# mosfet.net
KiCad netlist of a schematic drawn in EAGLE
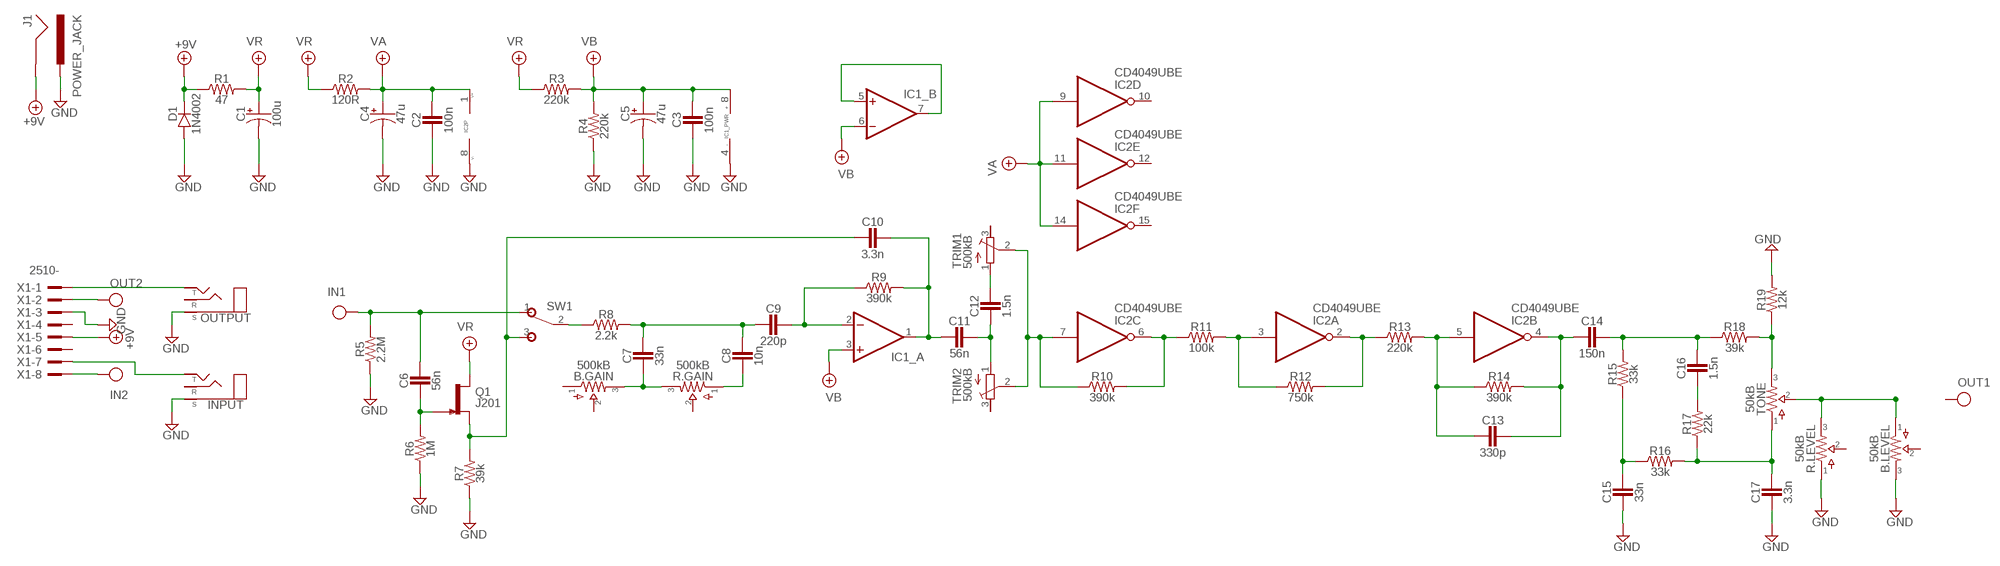
[diagram p0: schematic, sheet 1]

(export (version "E")
  (design (tool "Eeschema 10.0.6"))
  (components
    (comp (ref "B.GAIN")
      (value "500kB")
      (footprint "eagle-import:16MM")
      (libsource (lib "eagle-import") (part "POTS16MM"))
    )
    (comp (ref "B.LEVEL")
      (value "50kB")
      (footprint "eagle-import:16MM")
      (libsource (lib "eagle-import") (part "POTS16MM"))
    )
    (comp (ref "C1")
      (value "100u")
      (footprint "eagle-import:050_020")
      (libsource (lib "eagle-import") (part "0500"))
    )
    (comp (ref "C2")
      (value "100n")
      (footprint "eagle-import:050X030_025_2")
      (libsource (lib "eagle-import") (part "CER/FILM2"))
    )
    (comp (ref "C3")
      (value "100n")
      (footprint "eagle-import:050X030_025_2")
      (libsource (lib "eagle-import") (part "CER/FILM2"))
    )
    (comp (ref "C4")
      (value "47u")
      (footprint "eagle-import:050_020")
      (libsource (lib "eagle-import") (part "0500"))
    )
    (comp (ref "C5")
      (value "47u")
      (footprint "eagle-import:050_020")
      (libsource (lib "eagle-import") (part "0500"))
    )
    (comp (ref "C6")
      (value "56n")
      (footprint "eagle-import:BOX_SMALL")
      (libsource (lib "eagle-import") (part "CER/FILMBOX.1"))
    )
    (comp (ref "C7")
      (value "33n")
      (footprint "eagle-import:BOX_SMALL")
      (libsource (lib "eagle-import") (part "CER/FILMBOX.1"))
    )
    (comp (ref "C8")
      (value "10n")
      (footprint "eagle-import:BOX_SMALL")
      (libsource (lib "eagle-import") (part "CER/FILMBOX.1"))
    )
    (comp (ref "C9")
      (value "220p")
      (footprint "eagle-import:050X030_025_2")
      (libsource (lib "eagle-import") (part "CER/FILM2"))
    )
    (comp (ref "C10")
      (value "3.3n")
      (footprint "eagle-import:050X030_025_2")
      (libsource (lib "eagle-import") (part "CER/FILM2"))
    )
    (comp (ref "C11")
      (value "56n")
      (footprint "eagle-import:050X030_025_2")
      (libsource (lib "eagle-import") (part "CER/FILM2"))
    )
    (comp (ref "C12")
      (value "1.5n")
      (footprint "eagle-import:050X030_025_2")
      (libsource (lib "eagle-import") (part "CER/FILM2"))
    )
    (comp (ref "C13")
      (value "330p")
      (footprint "eagle-import:050X030_025_2")
      (libsource (lib "eagle-import") (part "CER/FILM2"))
    )
    (comp (ref "C14")
      (value "150n")
      (footprint "eagle-import:050X030_025_2")
      (libsource (lib "eagle-import") (part "CER/FILM2"))
    )
    (comp (ref "C15")
      (value "33n")
      (footprint "eagle-import:050X030_025_2")
      (libsource (lib "eagle-import") (part "CER/FILM2"))
    )
    (comp (ref "C16")
      (value "1.5n")
      (footprint "eagle-import:050X030_025_2")
      (libsource (lib "eagle-import") (part "CER/FILM2"))
    )
    (comp (ref "C17")
      (value "3.3n")
      (footprint "eagle-import:050X030_025_2")
      (libsource (lib "eagle-import") (part "CER/FILM2"))
    )
    (comp (ref "D1")
      (value "1N4002")
      (footprint "eagle-import:DO41-2")
      (libsource (lib "eagle-import") (part "DO41.2"))
    )
    (comp (ref "IC1")
      (value "DUALTH")
      (footprint "eagle-import:DIL0")
      (libsource (lib "eagle-import") (part "DUALTH"))
    )
    (comp (ref "IC2")
      (value "CD4049UBE")
      (footprint "eagle-import:DIL16")
      (libsource (lib "eagle-import") (part "CD4049UBE"))
    )
    (comp (ref "INPUT")
      (value "STEREONMJ")
      (footprint "eagle-import:NMJ6HCD2")
      (libsource (lib "eagle-import") (part "STEREONMJ"))
    )
    (comp (ref "J1")
      (value "POWER_JACK")
      (footprint "eagle-import:POWER_JACK_PTH")
      (libsource (lib "eagle-import") (part "POWER_JACK"))
    )
    (comp (ref "OUTPUT")
      (value "STEREONMJ")
      (footprint "eagle-import:NMJ6HCD2")
      (libsource (lib "eagle-import") (part "STEREONMJ"))
    )
    (comp (ref "Q1")
      (value "J201")
      (footprint "eagle-import:TO92-")
      (libsource (lib "eagle-import") (part "J201"))
    )
    (comp (ref "R.GAIN")
      (value "500kB")
      (footprint "eagle-import:16MM")
      (libsource (lib "eagle-import") (part "POTS16MM"))
    )
    (comp (ref "R.LEVEL")
      (value "50kB")
      (footprint "eagle-import:16MM")
      (libsource (lib "eagle-import") (part "POTS16MM"))
    )
    (comp (ref "R1")
      (value "47")
      (footprint "eagle-import:R0207_3")
      (libsource (lib "eagle-import") (part "R_.3B"))
    )
    (comp (ref "R2")
      (value "120R")
      (footprint "eagle-import:R0207_3")
      (libsource (lib "eagle-import") (part "R_.3B"))
    )
    (comp (ref "R3")
      (value "220k")
      (footprint "eagle-import:R0207_3")
      (libsource (lib "eagle-import") (part "R_.3B"))
    )
    (comp (ref "R4")
      (value "220k")
      (footprint "eagle-import:R0207_3")
      (libsource (lib "eagle-import") (part "R_.3B"))
    )
    (comp (ref "R5")
      (value "2.2M")
      (footprint "eagle-import:R0207_3")
      (libsource (lib "eagle-import") (part "R_.3B"))
    )
    (comp (ref "R6")
      (value "1M")
      (footprint "eagle-import:R0207_3")
      (libsource (lib "eagle-import") (part "R_.3B"))
    )
    (comp (ref "R7")
      (value "39k")
      (footprint "eagle-import:R0207_3")
      (libsource (lib "eagle-import") (part "R_.3B"))
    )
    (comp (ref "R8")
      (value "2.2k")
      (footprint "eagle-import:R0207_3")
      (libsource (lib "eagle-import") (part "R_.3B"))
    )
    (comp (ref "R9")
      (value "390k")
      (footprint "eagle-import:R0207_3")
      (libsource (lib "eagle-import") (part "R_.3B"))
    )
    (comp (ref "R10")
      (value "390k")
      (footprint "eagle-import:R0207_3")
      (libsource (lib "eagle-import") (part "R_.3B"))
    )
    (comp (ref "R11")
      (value "100k")
      (footprint "eagle-import:R0207_3")
      (libsource (lib "eagle-import") (part "R_.3B"))
    )
    (comp (ref "R12")
      (value "750k")
      (footprint "eagle-import:R0207_3")
      (libsource (lib "eagle-import") (part "R_.3B"))
    )
    (comp (ref "R13")
      (value "220k")
      (footprint "eagle-import:R0207_3")
      (libsource (lib "eagle-import") (part "R_.3B"))
    )
    (comp (ref "R14")
      (value "390k")
      (footprint "eagle-import:R0207_3")
      (libsource (lib "eagle-import") (part "R_.3B"))
    )
    (comp (ref "R15")
      (value "33k")
      (footprint "eagle-import:R0207_3")
      (libsource (lib "eagle-import") (part "R_.3B"))
    )
    (comp (ref "R16")
      (value "33k")
      (footprint "eagle-import:R0207_3")
      (libsource (lib "eagle-import") (part "R_.3B"))
    )
    (comp (ref "R17")
      (value "22k")
      (footprint "eagle-import:R0207_3")
      (libsource (lib "eagle-import") (part "R_.3B"))
    )
    (comp (ref "R18")
      (value "39k")
      (footprint "eagle-import:R0207_3")
      (libsource (lib "eagle-import") (part "R_.3B"))
    )
    (comp (ref "R19")
      (value "12k")
      (footprint "eagle-import:R0207_3")
      (libsource (lib "eagle-import") (part "R_.3B"))
    )
    (comp (ref "SW1")
      (value "SPDT")
      (footprint "eagle-import:M9040P")
      (libsource (lib "eagle-import") (part "SPDT"))
    )
    (comp (ref "TONE")
      (value "50kB")
      (footprint "eagle-import:16MM")
      (libsource (lib "eagle-import") (part "POTS16MM"))
    )
    (comp (ref "TRIM1")
      (value "500kB")
      (footprint "eagle-import:RTRIM3296W")
      (libsource (lib "eagle-import") (part "R-TRIMM3296W"))
    )
    (comp (ref "TRIM2")
      (value "500kB")
      (footprint "eagle-import:RTRIM3296W")
      (libsource (lib "eagle-import") (part "R-TRIMM3296W"))
    )
    (comp (ref "X1")
      (value "2510-")
      (footprint "eagle-import:PAK100_2500-10")
      (fields (field (name "MF") "3M") (field (name "MPN") "2510-6002UB"))
      (libsource (lib "eagle-import") (part "2510-"))
    )
  )
  (nets
    (net (code "1") (name "+9V") (class "Default")
      (node (ref "D1") (pin "C") (pinfunction "C_C") (pintype "passive"))
      (node (ref "J1") (pin "GND") (pinfunction "GND_GND") (pintype "bidirectional"))
      (node (ref "R1") (pin "1") (pinfunction "1_1") (pintype "passive"))
      (node (ref "X1") (pin "5") (pinfunction "KL_5") (pintype "passive"))
    )
    (net (code "2") (name "GND") (class "Default")
      (node (ref "B.LEVEL") (pin "3") (pinfunction "3_3") (pintype "passive"))
      (node (ref "C1") (pin "-") (pinfunction "-_-") (pintype "passive"))
      (node (ref "C15") (pin "1") (pinfunction "1_1") (pintype "passive"))
      (node (ref "C17") (pin "1") (pinfunction "1_1") (pintype "passive"))
      (node (ref "C2") (pin "1") (pinfunction "1_1") (pintype "passive"))
      (node (ref "C3") (pin "1") (pinfunction "1_1") (pintype "passive"))
      (node (ref "C4") (pin "-") (pinfunction "-_-") (pintype "passive"))
      (node (ref "C5") (pin "-") (pinfunction "-_-") (pintype "passive"))
      (node (ref "D1") (pin "A") (pinfunction "A_A") (pintype "passive"))
      (node (ref "IC1") (pin "4") (pinfunction "V-_4") (pintype "power_in"))
      (node (ref "IC2") (pin "8") (pinfunction "VSS_8") (pintype "power_in"))
      (node (ref "INPUT") (pin "S") (pinfunction "S_S") (pintype "passive"))
      (node (ref "J1") (pin "PWR") (pinfunction "PWR_PWR") (pintype "bidirectional"))
      (node (ref "OUTPUT") (pin "S") (pinfunction "S_S") (pintype "passive"))
      (node (ref "R.LEVEL") (pin "1") (pinfunction "1_1") (pintype "passive"))
      (node (ref "R19") (pin "2") (pinfunction "2_2") (pintype "passive"))
      (node (ref "R4") (pin "1") (pinfunction "1_1") (pintype "passive"))
      (node (ref "R5") (pin "1") (pinfunction "1_1") (pintype "passive"))
      (node (ref "R6") (pin "1") (pinfunction "1_1") (pintype "passive"))
      (node (ref "R7") (pin "1") (pinfunction "1_1") (pintype "passive"))
      (node (ref "X1") (pin "3") (pinfunction "KL_3") (pintype "passive"))
    )
    (net (code "3") (name "IN") (class "Default")
      (node (ref "C6") (pin "2") (pinfunction "2_2") (pintype "passive"))
      (node (ref "R5") (pin "2") (pinfunction "2_2") (pintype "passive"))
      (node (ref "SW1") (pin "1") (pinfunction "O_1") (pintype "passive"))
      (node (ref "X1") (pin "8") (pinfunction "KL_8") (pintype "passive"))
    )
    (net (code "4") (name "Net-(B.GAIN-Pad3)") (class "Default")
      (node (ref "B.GAIN") (pin "3") (pinfunction "3_3") (pintype "passive"))
      (node (ref "C7") (pin "1") (pinfunction "1_1") (pintype "passive"))
      (node (ref "R.GAIN") (pin "3") (pinfunction "3_3") (pintype "passive"))
    )
    (net (code "5") (name "Net-(B.LEVEL-Pad1)") (class "Default")
      (node (ref "B.LEVEL") (pin "1") (pinfunction "1_1") (pintype "passive"))
      (node (ref "R.LEVEL") (pin "3") (pinfunction "3_3") (pintype "passive"))
      (node (ref "TONE") (pin "2") (pinfunction "2_2") (pintype "passive"))
    )
    (net (code "6") (name "Net-(C7-Pad2)") (class "Default")
      (node (ref "C7") (pin "2") (pinfunction "2_2") (pintype "passive"))
      (node (ref "C8") (pin "2") (pinfunction "2_2") (pintype "passive"))
      (node (ref "C9") (pin "1") (pinfunction "1_1") (pintype "passive"))
      (node (ref "R8") (pin "2") (pinfunction "2_2") (pintype "passive"))
    )
    (net (code "7") (name "Net-(C8-Pad1)") (class "Default")
      (node (ref "C8") (pin "1") (pinfunction "1_1") (pintype "passive"))
      (node (ref "R.GAIN") (pin "1") (pinfunction "1_1") (pintype "passive"))
    )
    (net (code "8") (name "Net-(C14-Pad2)") (class "Default")
      (node (ref "C14") (pin "2") (pinfunction "2_2") (pintype "passive"))
      (node (ref "C16") (pin "2") (pinfunction "2_2") (pintype "passive"))
      (node (ref "R15") (pin "2") (pinfunction "2_2") (pintype "passive"))
      (node (ref "R18") (pin "1") (pinfunction "1_1") (pintype "passive"))
    )
    (net (code "9") (name "Net-(C15-Pad2)") (class "Default")
      (node (ref "C15") (pin "2") (pinfunction "2_2") (pintype "passive"))
      (node (ref "R15") (pin "1") (pinfunction "1_1") (pintype "passive"))
      (node (ref "R16") (pin "1") (pinfunction "1_1") (pintype "passive"))
    )
    (net (code "10") (name "Net-(C16-Pad1)") (class "Default")
      (node (ref "C16") (pin "1") (pinfunction "1_1") (pintype "passive"))
      (node (ref "R17") (pin "2") (pinfunction "2_2") (pintype "passive"))
    )
    (net (code "11") (name "Net-(C17-Pad2)") (class "Default")
      (node (ref "C17") (pin "2") (pinfunction "2_2") (pintype "passive"))
      (node (ref "R16") (pin "2") (pinfunction "2_2") (pintype "passive"))
      (node (ref "R17") (pin "1") (pinfunction "1_1") (pintype "passive"))
      (node (ref "TONE") (pin "1") (pinfunction "1_1") (pintype "passive"))
    )
    (net (code "12") (name "Net-(IC1A--IN)") (class "Default")
      (node (ref "C9") (pin "2") (pinfunction "2_2") (pintype "passive"))
      (node (ref "IC1") (pin "2") (pinfunction "-IN_2") (pintype "input"))
      (node (ref "R9") (pin "1") (pinfunction "1_1") (pintype "passive"))
    )
    (net (code "13") (name "Net-(IC1A-OUT)") (class "Default")
      (node (ref "C10") (pin "2") (pinfunction "2_2") (pintype "passive"))
      (node (ref "C11") (pin "1") (pinfunction "1_1") (pintype "passive"))
      (node (ref "IC1") (pin "1") (pinfunction "OUT_1") (pintype "output"))
      (node (ref "R9") (pin "2") (pinfunction "2_2") (pintype "passive"))
    )
    (net (code "14") (name "Net-(IC1B-+IN)") (class "Default")
      (node (ref "IC1") (pin "5") (pinfunction "+IN_5") (pintype "input"))
      (node (ref "IC1") (pin "7") (pinfunction "OUT_7") (pintype "output"))
    )
    (net (code "15") (name "Net-(IC2A-I)") (class "Default")
      (node (ref "IC2") (pin "3") (pinfunction "I_3") (pintype "input"))
      (node (ref "R11") (pin "2") (pinfunction "2_2") (pintype "passive"))
      (node (ref "R12") (pin "1") (pinfunction "1_1") (pintype "passive"))
    )
    (net (code "16") (name "Net-(IC2A-O)") (class "Default")
      (node (ref "IC2") (pin "2") (pinfunction "O_2") (pintype "output"))
      (node (ref "R12") (pin "2") (pinfunction "2_2") (pintype "passive"))
      (node (ref "R13") (pin "1") (pinfunction "1_1") (pintype "passive"))
    )
    (net (code "17") (name "Net-(IC2B-I)") (class "Default")
      (node (ref "C13") (pin "1") (pinfunction "1_1") (pintype "passive"))
      (node (ref "IC2") (pin "5") (pinfunction "I_5") (pintype "input"))
      (node (ref "R13") (pin "2") (pinfunction "2_2") (pintype "passive"))
      (node (ref "R14") (pin "1") (pinfunction "1_1") (pintype "passive"))
    )
    (net (code "18") (name "Net-(IC2B-O)") (class "Default")
      (node (ref "C13") (pin "2") (pinfunction "2_2") (pintype "passive"))
      (node (ref "C14") (pin "1") (pinfunction "1_1") (pintype "passive"))
      (node (ref "IC2") (pin "4") (pinfunction "O_4") (pintype "output"))
      (node (ref "R14") (pin "2") (pinfunction "2_2") (pintype "passive"))
    )
    (net (code "19") (name "Net-(IC2C-I)") (class "Default")
      (node (ref "IC2") (pin "7") (pinfunction "I_7") (pintype "input"))
      (node (ref "R10") (pin "1") (pinfunction "1_1") (pintype "passive"))
      (node (ref "TRIM1") (pin "2") (pinfunction "S_2") (pintype "passive"))
      (node (ref "TRIM2") (pin "2") (pinfunction "S_2") (pintype "passive"))
    )
    (net (code "20") (name "Net-(IC2C-O)") (class "Default")
      (node (ref "IC2") (pin "6") (pinfunction "O_6") (pintype "output"))
      (node (ref "R10") (pin "2") (pinfunction "2_2") (pintype "passive"))
      (node (ref "R11") (pin "1") (pinfunction "1_1") (pintype "passive"))
    )
    (net (code "21") (name "Net-(Q1-G)") (class "Default")
      (node (ref "C6") (pin "1") (pinfunction "1_1") (pintype "passive"))
      (node (ref "Q1") (pin "1") (pinfunction "G_1") (pintype "passive"))
      (node (ref "R6") (pin "2") (pinfunction "2_2") (pintype "passive"))
    )
    (net (code "22") (name "Net-(Q1-S)") (class "Default")
      (node (ref "C10") (pin "1") (pinfunction "1_1") (pintype "passive"))
      (node (ref "Q1") (pin "2") (pinfunction "S_2") (pintype "passive"))
      (node (ref "R7") (pin "2") (pinfunction "2_2") (pintype "passive"))
      (node (ref "SW1") (pin "3") (pinfunction "S_3") (pintype "passive"))
    )
    (net (code "23") (name "Net-(R18-Pad2)") (class "Default")
      (node (ref "R18") (pin "2") (pinfunction "2_2") (pintype "passive"))
      (node (ref "R19") (pin "1") (pinfunction "1_1") (pintype "passive"))
      (node (ref "TONE") (pin "3") (pinfunction "3_3") (pintype "passive"))
    )
    (net (code "24") (name "Net-(SW1-P)") (class "Default")
      (node (ref "R8") (pin "1") (pinfunction "1_1") (pintype "passive"))
      (node (ref "SW1") (pin "2") (pinfunction "P_2") (pintype "passive"))
    )
    (net (code "25") (name "Net-(TRIM1-A)") (class "Default")
      (node (ref "C12") (pin "2") (pinfunction "2_2") (pintype "passive"))
      (node (ref "TRIM1") (pin "1") (pinfunction "A_1") (pintype "passive"))
    )
    (net (code "26") (name "Net-(TRIM2-A)") (class "Default")
      (node (ref "C11") (pin "2") (pinfunction "2_2") (pintype "passive"))
      (node (ref "C12") (pin "1") (pinfunction "1_1") (pintype "passive"))
      (node (ref "TRIM2") (pin "1") (pinfunction "A_1") (pintype "passive"))
    )
    (net (code "27") (name "Net-(X1A-KL)") (class "Default")
      (node (ref "OUTPUT") (pin "T") (pinfunction "T_T") (pintype "passive"))
      (node (ref "X1") (pin "1") (pinfunction "KL_1") (pintype "passive"))
    )
    (net (code "28") (name "Net-(X1G-KL)") (class "Default")
      (node (ref "INPUT") (pin "T") (pinfunction "T_T") (pintype "passive"))
      (node (ref "X1") (pin "7") (pinfunction "KL_7") (pintype "passive"))
    )
    (net (code "29") (name "OUT") (class "Default")
      (node (ref "X1") (pin "2") (pinfunction "KL_2") (pintype "passive"))
    )
    (net (code "30") (name "VA") (class "Default")
      (node (ref "C2") (pin "2") (pinfunction "2_2") (pintype "passive"))
      (node (ref "C4") (pin "+") (pinfunction "+_+") (pintype "passive"))
      (node (ref "IC2") (pin "1") (pinfunction "VDD_1") (pintype "power_in"))
      (node (ref "IC2") (pin "11") (pinfunction "I_11") (pintype "input"))
      (node (ref "IC2") (pin "14") (pinfunction "I_14") (pintype "input"))
      (node (ref "IC2") (pin "9") (pinfunction "I_9") (pintype "input"))
      (node (ref "R2") (pin "2") (pinfunction "2_2") (pintype "passive"))
    )
    (net (code "31") (name "VB") (class "Default")
      (node (ref "C3") (pin "2") (pinfunction "2_2") (pintype "passive"))
      (node (ref "C5") (pin "+") (pinfunction "+_+") (pintype "passive"))
      (node (ref "IC1") (pin "3") (pinfunction "+IN_3") (pintype "input"))
      (node (ref "IC1") (pin "6") (pinfunction "-IN_6") (pintype "input"))
      (node (ref "IC1") (pin "8") (pinfunction "V+_8") (pintype "power_in"))
      (node (ref "R3") (pin "2") (pinfunction "2_2") (pintype "passive"))
      (node (ref "R4") (pin "2") (pinfunction "2_2") (pintype "passive"))
    )
    (net (code "32") (name "VR") (class "Default")
      (node (ref "C1") (pin "+") (pinfunction "+_+") (pintype "passive"))
      (node (ref "Q1") (pin "3") (pinfunction "D_3") (pintype "passive"))
      (node (ref "R1") (pin "2") (pinfunction "2_2") (pintype "passive"))
      (node (ref "R2") (pin "1") (pinfunction "1_1") (pintype "passive"))
      (node (ref "R3") (pin "1") (pinfunction "1_1") (pintype "passive"))
    )
    (net (code "33") (name "unconnected-(B.GAIN-Pad1)") (class "Default")
      (node (ref "B.GAIN") (pin "1") (pinfunction "1_1") (pintype "passive"))
    )
    (net (code "34") (name "unconnected-(B.GAIN-Pad2)") (class "Default")
      (node (ref "B.GAIN") (pin "2") (pinfunction "2_2") (pintype "passive"))
    )
    (net (code "35") (name "unconnected-(B.LEVEL-Pad2)") (class "Default")
      (node (ref "B.LEVEL") (pin "2") (pinfunction "2_2") (pintype "passive"))
    )
    (net (code "36") (name "unconnected-(IC2D-O-Pad10)") (class "Default")
      (node (ref "IC2") (pin "10") (pinfunction "O_10") (pintype "output"))
    )
    (net (code "37") (name "unconnected-(IC2E-O-Pad12)") (class "Default")
      (node (ref "IC2") (pin "12") (pinfunction "O_12") (pintype "output"))
    )
    (net (code "38") (name "unconnected-(IC2F-O-Pad15)") (class "Default")
      (node (ref "IC2") (pin "15") (pinfunction "O_15") (pintype "output"))
    )
    (net (code "39") (name "unconnected-(INPUT-PadR)") (class "Default")
      (node (ref "INPUT") (pin "R") (pinfunction "R_R") (pintype "passive"))
    )
    (net (code "40") (name "unconnected-(OUTPUT-PadR)") (class "Default")
      (node (ref "OUTPUT") (pin "R") (pinfunction "R_R") (pintype "passive"))
    )
    (net (code "41") (name "unconnected-(R.GAIN-Pad2)") (class "Default")
      (node (ref "R.GAIN") (pin "2") (pinfunction "2_2") (pintype "passive"))
    )
    (net (code "42") (name "unconnected-(R.LEVEL-Pad2)") (class "Default")
      (node (ref "R.LEVEL") (pin "2") (pinfunction "2_2") (pintype "passive"))
    )
    (net (code "43") (name "unconnected-(TRIM1-E-Pad3)") (class "Default")
      (node (ref "TRIM1") (pin "3") (pinfunction "E_3") (pintype "passive"))
    )
    (net (code "44") (name "unconnected-(TRIM2-E-Pad3)") (class "Default")
      (node (ref "TRIM2") (pin "3") (pinfunction "E_3") (pintype "passive"))
    )
    (net (code "45") (name "unconnected-(X1D-KL-Pad4)") (class "Default")
      (node (ref "X1") (pin "4") (pinfunction "KL_4") (pintype "passive"))
    )
    (net (code "46") (name "unconnected-(X1F-KL-Pad6)") (class "Default")
      (node (ref "X1") (pin "6") (pinfunction "KL_6") (pintype "passive"))
    )
  )
)
